# connector-schematic.net
KiCad netlist of a schematic drawn in Altium Designer
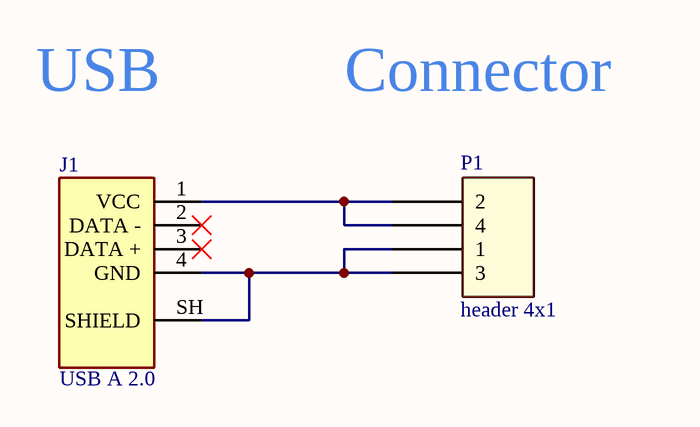
[diagram p0: connector-schematic.SchDoc]

(export (version "E")
  (design (tool "Eeschema 10.0.6"))
  (components
    (comp (ref "J1")
      (value "USB A 2.0")
      (footprint "0480372100")
      (description "Type A, USB 2.0, 1 A, Vertical, Through Hole, USB Receptacle")
      (fields (field (name "MP") "UJ2-AV-2-TH") (field (name "MF") "CUI Devices"))
      (libsource (lib "USBHUB") (part "USB A 2.0"))
    )
    (comp (ref "P1")
      (value "header 4x1")
      (footprint "4x1, 2.54mm, smd side")
      (libsource (lib "USBHUB") (part "header 4x1"))
    )
  )
  (nets
    (net (code "1") (name "Net-(J1-GND)") (class "Default")
      (node (ref "J1") (pin "4") (pinfunction "GND_4") (pintype "passive"))
      (node (ref "J1") (pin "SH") (pinfunction "SHIELD_SH") (pintype "passive"))
      (node (ref "P1") (pin "1") (pinfunction "1_1") (pintype "passive"))
      (node (ref "P1") (pin "3") (pinfunction "3_3") (pintype "passive"))
    )
    (net (code "2") (name "Net-(J1-VCC)") (class "Default")
      (node (ref "J1") (pin "1") (pinfunction "VCC_1") (pintype "passive"))
      (node (ref "P1") (pin "2") (pinfunction "2_2") (pintype "passive"))
      (node (ref "P1") (pin "4") (pinfunction "4_4") (pintype "passive"))
    )
    (net (code "3") (name "unconnected-(J1-DATA_+-Pad3)") (class "Default")
      (node (ref "J1") (pin "3") (pinfunction "DATA_+_3") (pintype "passive+no_connect"))
    )
    (net (code "4") (name "unconnected-(J1-DATA_--Pad2)") (class "Default")
      (node (ref "J1") (pin "2") (pinfunction "DATA_-_2") (pintype "passive+no_connect"))
    )
  )
)
